# dat.net
KiCad netlist of a schematic drawn in Altium Designer
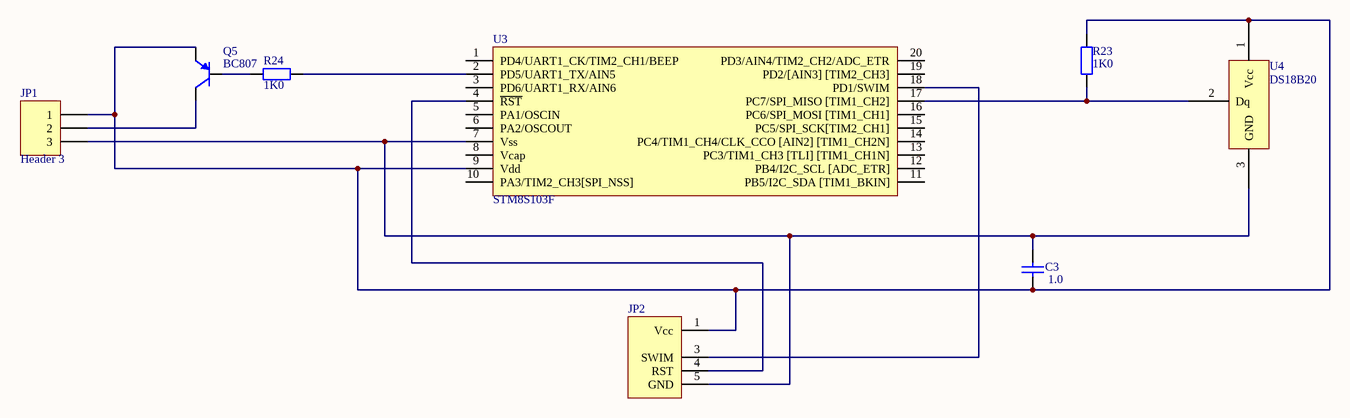
[diagram p0: dat.SchDoc]

(export (version "E")
  (design (tool "Eeschema 10.0.6"))
  (components
    (comp (ref "C3")
      (value "1.0")
      (footprint "_1206")
      (description "Capacitor")
      (fields (field (name "MANUFACTURER") "Generic Components") (field (name "PUBLISHER") "Altium Limited"))
      (libsource (lib "Miscellaneous Devices") (part "Cap Semi"))
    )
    (comp (ref "JP1")
      (value "Header 3")
      (footprint "BT5-3")
      (description "Header, 3-Pin")
      (fields (field (name "MANUFACTURER") "Generic Components") (field (name "PUBLISHER") "Altium Limited"))
      (libsource (lib "Miscellaneous Connectors") (part "Header 3"))
    )
    (comp (ref "JP2") (value "~") (footprint "HDR1X5_uart") (libsource (lib "PAL") (part "SWIM_CONN")))
    (comp (ref "Q5")
      (value "BC807")
      (footprint "SO-G3")
      (description "General Purpose Transistor PNP Silicon")
      (fields (field (name "MANUFACTURER") "Motorola") (field (name "PUBLISHER") "Altium Limited"))
      (libsource (lib "PAL") (part "BC857ALT1"))
    )
    (comp (ref "R23")
      (value "Res2")
      (footprint "_1206")
      (description "Resistor")
      (fields
        (field (name "MANUFACTURER") "Generic Components")
        (field (name "ALTIUM_VALUE") "1K0")
        (field (name "PUBLISHER") "Altium Limited")
      )
      (libsource (lib "Miscellaneous Devices") (part "Res2"))
    )
    (comp (ref "R24")
      (value "Res2")
      (footprint "_1206")
      (description "Resistor")
      (fields
        (field (name "MANUFACTURER") "Generic Components")
        (field (name "ALTIUM_VALUE") "1K0")
        (field (name "PUBLISHER") "Altium Limited")
      )
      (libsource (lib "") (part "Res2_1"))
    )
    (comp (ref "U3") (value "~") (footprint "TSSO6x6-G20/Y1.6") (libsource (lib "PAL") (part "STM8S103F")))
    (comp (ref "U4") (value "DS18B20") (footprint "DS18B20_H") (libsource (lib "PAL") (part "DS18B20")))
  )
  (nets
    (net (code "1") (name "Net-(JP2-GND)") (class "Default")
      (node (ref "C3") (pin "2") (pinfunction "2_2") (pintype "passive"))
      (node (ref "JP1") (pin "3") (pinfunction "3_3") (pintype "passive"))
      (node (ref "JP2") (pin "5") (pinfunction "GND_5") (pintype "passive"))
      (node (ref "U3") (pin "7") (pinfunction "Vss_7") (pintype "passive"))
      (node (ref "U4") (pin "3") (pinfunction "GND_3") (pintype "passive"))
    )
    (net (code "2") (name "Net-(JP2-RST)") (class "Default")
      (node (ref "JP2") (pin "4") (pinfunction "RST_4") (pintype "passive"))
      (node (ref "U3") (pin "4") (pinfunction "~{RST}_4") (pintype "passive"))
    )
    (net (code "3") (name "Net-(JP2-SWIM)") (class "Default")
      (node (ref "JP2") (pin "3") (pinfunction "SWIM_3") (pintype "passive"))
      (node (ref "U3") (pin "18") (pinfunction "PD1/SWIM_18") (pintype "passive"))
    )
    (net (code "4") (name "Net-(JP2-Vcc)") (class "Default")
      (node (ref "C3") (pin "1") (pinfunction "1_1") (pintype "passive"))
      (node (ref "JP1") (pin "1") (pinfunction "1_1") (pintype "passive"))
      (node (ref "JP2") (pin "1") (pinfunction "Vcc_1") (pintype "passive"))
      (node (ref "Q5") (pin "2") (pinfunction "E_2") (pintype "passive"))
      (node (ref "R23") (pin "1") (pinfunction "1_1") (pintype "passive"))
      (node (ref "U3") (pin "9") (pinfunction "Vdd_9") (pintype "passive"))
      (node (ref "U4") (pin "1") (pinfunction "Vcc_1") (pintype "passive"))
    )
    (net (code "5") (name "Net-(Q5-B)") (class "Default")
      (node (ref "Q5") (pin "1") (pinfunction "B_1") (pintype "passive"))
      (node (ref "R24") (pin "2") (pinfunction "2_2") (pintype "passive"))
    )
    (net (code "6") (name "Net-(Q5-C)") (class "Default")
      (node (ref "JP1") (pin "2") (pinfunction "2_2") (pintype "passive"))
      (node (ref "Q5") (pin "3") (pinfunction "C_3") (pintype "passive"))
    )
    (net (code "7") (name "Net-(U3-PC7{slash}SPI_MISO_[TIM1_CH2])") (class "Default")
      (node (ref "R23") (pin "2") (pinfunction "2_2") (pintype "passive"))
      (node (ref "U3") (pin "17") (pinfunction "PC7/SPI_MISO_[TIM1_CH2]_17") (pintype "passive"))
      (node (ref "U4") (pin "2") (pinfunction "Dq_2") (pintype "passive"))
    )
    (net (code "8") (name "Net-(U3-PD5{slash}UART1_TX{slash}AIN5)") (class "Default")
      (node (ref "R24") (pin "1") (pinfunction "1_1") (pintype "passive"))
      (node (ref "U3") (pin "2") (pinfunction "PD5/UART1_TX/AIN5_2") (pintype "passive"))
    )
    (net (code "9") (name "unconnected-(U3-PA1{slash}OSCIN-Pad5)") (class "Default")
      (node (ref "U3") (pin "5") (pinfunction "PA1/OSCIN_5") (pintype "passive"))
    )
    (net (code "10") (name "unconnected-(U3-PA2{slash}OSCOUT-Pad6)") (class "Default")
      (node (ref "U3") (pin "6") (pinfunction "PA2/OSCOUT_6") (pintype "passive"))
    )
    (net (code "11") (name "unconnected-(U3-PA3{slash}TIM2_CH3[SPI_NSS]-Pad10)") (class "Default")
      (node (ref "U3") (pin "10") (pinfunction "PA3/TIM2_CH3[SPI_NSS]_10") (pintype "passive"))
    )
    (net (code "12") (name "unconnected-(U3-PB4{slash}I2C_SCL_[ADC_ETR]-Pad12)") (class "Default")
      (node (ref "U3") (pin "12") (pinfunction "PB4/I2C_SCL_[ADC_ETR]_12") (pintype "passive"))
    )
    (net (code "13") (name "unconnected-(U3-PB5{slash}I2C_SDA_[TIM1_BKIN]-Pad11)") (class "Default")
      (node (ref "U3") (pin "11") (pinfunction "PB5/I2C_SDA_[TIM1_BKIN]_11") (pintype "passive"))
    )
    (net (code "14") (name "unconnected-(U3-PC3{slash}TIM1_CH3_[TLI]_[TIM1_CH1N]-Pad13)") (class "Default")
      (node (ref "U3") (pin "13") (pinfunction "PC3/TIM1_CH3_[TLI]_[TIM1_CH1N]_13") (pintype "passive"))
    )
    (net (code "15") (name "unconnected-(U3-PC4{slash}TIM1_CH4{slash}CLK_CCO_[AIN2]_[TIM1_CH2N]-Pad14)") (class "Default")
      (node (ref "U3") (pin "14") (pinfunction "PC4/TIM1_CH4/CLK_CCO_[AIN2]_[TIM1_CH2N]_14") (pintype "passive"))
    )
    (net (code "16") (name "unconnected-(U3-PC5{slash}SPI_SCK[TIM2_CH1]-Pad15)") (class "Default")
      (node (ref "U3") (pin "15") (pinfunction "PC5/SPI_SCK[TIM2_CH1]_15") (pintype "passive"))
    )
    (net (code "17") (name "unconnected-(U3-PC6{slash}SPI_MOSI_[TIM1_CH1]-Pad16)") (class "Default")
      (node (ref "U3") (pin "16") (pinfunction "PC6/SPI_MOSI_[TIM1_CH1]_16") (pintype "passive"))
    )
    (net (code "18") (name "unconnected-(U3-PD2{slash}[AIN3]_[TIM2_CH3]-Pad19)") (class "Default")
      (node (ref "U3") (pin "19") (pinfunction "PD2/[AIN3]_[TIM2_CH3]_19") (pintype "passive"))
    )
    (net (code "19") (name "unconnected-(U3-PD3{slash}AIN4{slash}TIM2_CH2{slash}ADC_ETR-Pad20)") (class "Default")
      (node (ref "U3") (pin "20") (pinfunction "PD3/AIN4/TIM2_CH2/ADC_ETR_20") (pintype "passive"))
    )
    (net (code "20") (name "unconnected-(U3-PD4{slash}UART1_CK{slash}TIM2_CH1{slash}BEEP-Pad1)") (class "Default")
      (node (ref "U3") (pin "1") (pinfunction "PD4/UART1_CK/TIM2_CH1/BEEP_1") (pintype "passive"))
    )
    (net (code "21") (name "unconnected-(U3-PD6{slash}UART1_RX{slash}AIN6-Pad3)") (class "Default")
      (node (ref "U3") (pin "3") (pinfunction "PD6/UART1_RX/AIN6_3") (pintype "passive"))
    )
    (net (code "22") (name "unconnected-(U3-Vcap-Pad8)") (class "Default")
      (node (ref "U3") (pin "8") (pinfunction "Vcap_8") (pintype "passive"))
    )
  )
)
